# espyolsuz.net
KiCad netlist of a schematic drawn in EAGLE
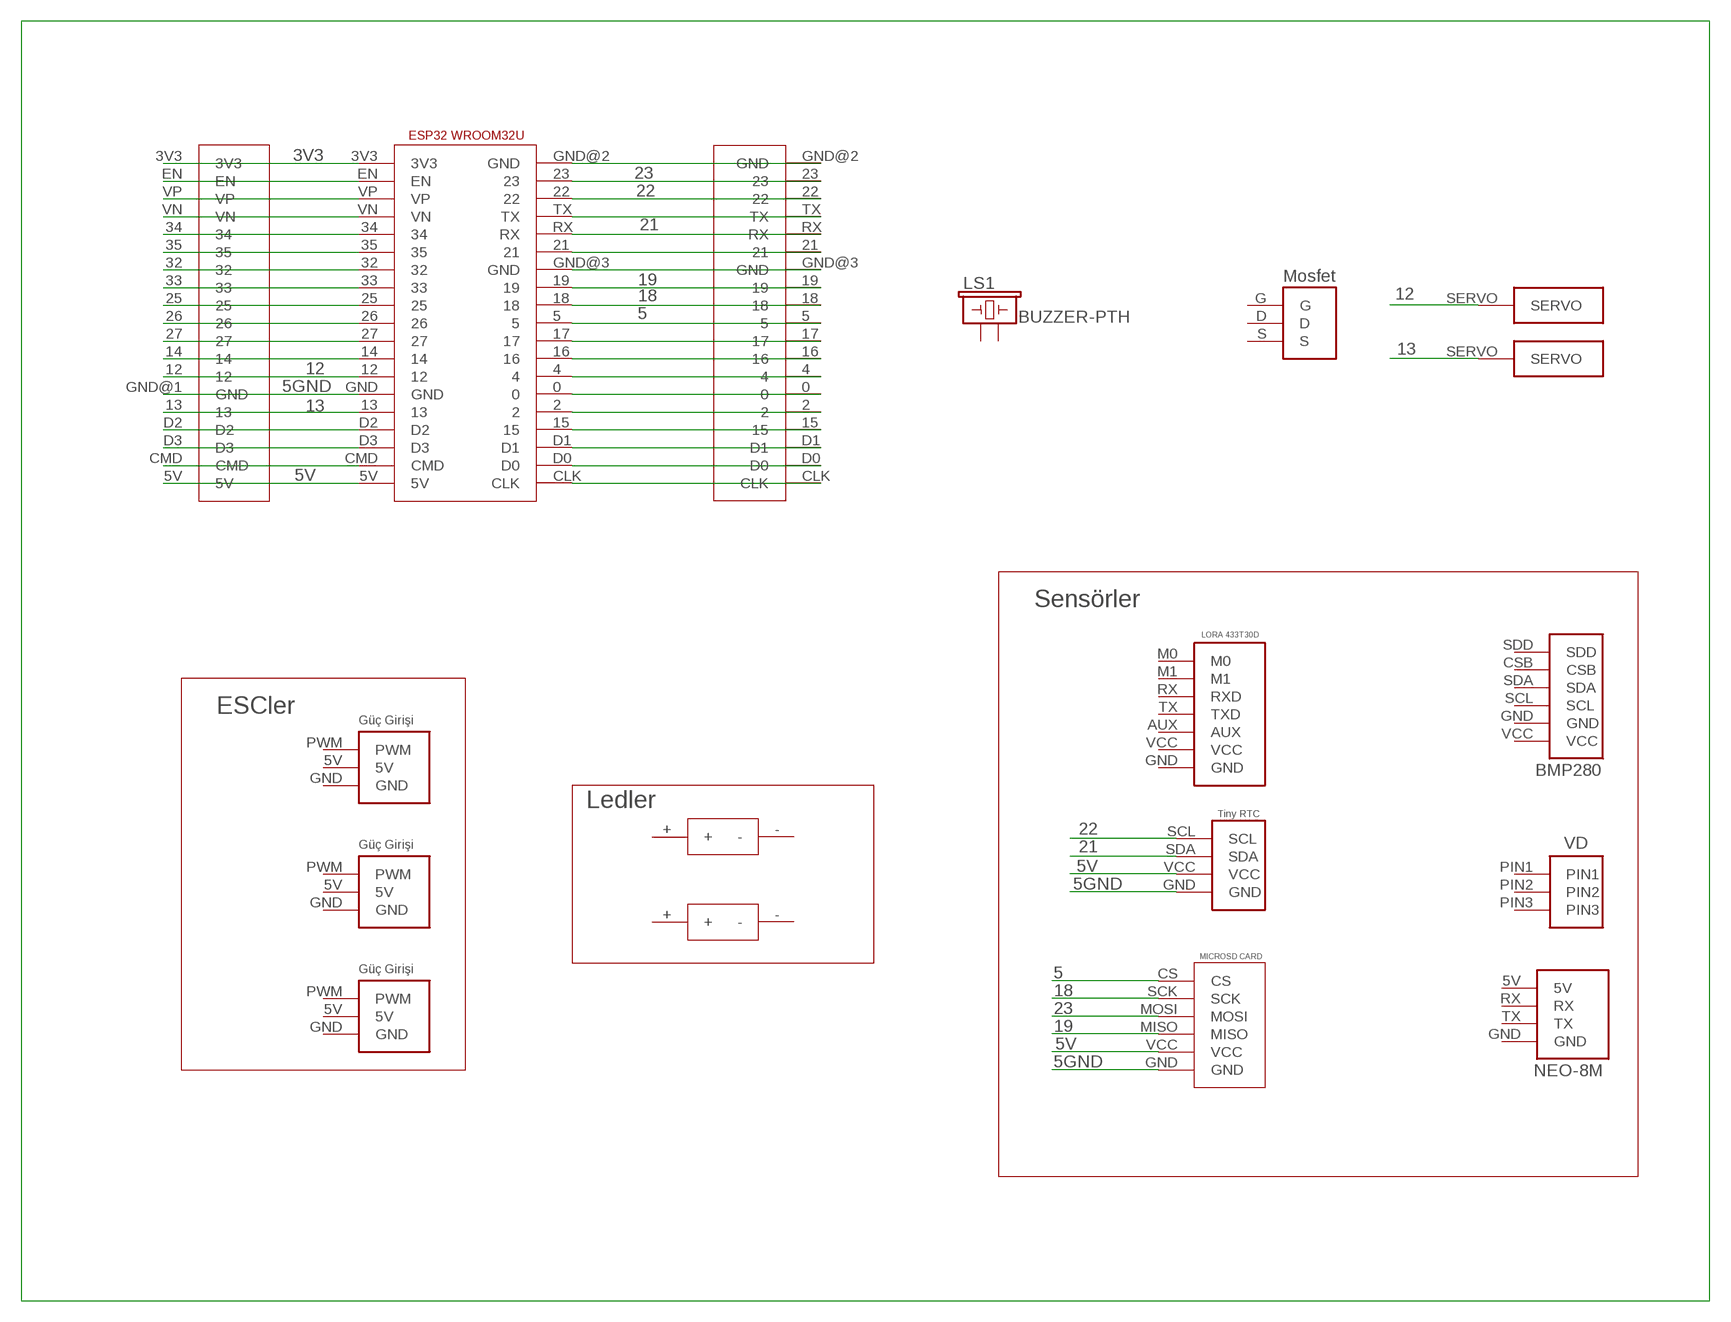
[diagram p0: schematic, sheet 1]

(export (version "E")
  (design (tool "Eeschema 10.0.6"))
  (components
    (comp (ref "BMP1")
      (value "BMP280")
      (footprint "eagle-import:BMP280")
      (libsource (lib "eagle-import") (part "BMP280"))
    )
    (comp (ref "LS1")
      (value "BUZZER-PTH")
      (footprint "eagle-import:BUZZER-12MM")
      (libsource (lib "eagle-import") (part "BUZZER-PTH"))
    )
    (comp (ref "U$1")
      (value "TINYRTC")
      (footprint "eagle-import:TINYRTC")
      (libsource (lib "eagle-import") (part "TINYRTC"))
    )
    (comp (ref "U$2")
      (value "VOLTAGE_DIVIDER")
      (footprint "eagle-import:VOLTAGE_DIVIDER")
      (libsource (lib "eagle-import") (part "VOLTAGE_DIVIDER"))
    )
    (comp (ref "U$3")
      (value "NEOM8N")
      (footprint "eagle-import:NEO8M")
      (libsource (lib "eagle-import") (part "NEOM8N"))
    )
    (comp (ref "U$4")
      (value "ESP32WROOM32U")
      (footprint "eagle-import:ESP32WROOM32U")
      (libsource (lib "eagle-import") (part "ESP32WROOM32U"))
    )
    (comp (ref "U$5")
      (value "LORAFULLSIZE")
      (footprint "eagle-import:LORAFULLSIZE")
      (libsource (lib "eagle-import") (part "LORAFULLSIZE"))
    )
    (comp (ref "U$6")
      (value "MICROSD_CARD")
      (footprint "eagle-import:MICROSD_CARD")
      (libsource (lib "eagle-import") (part "MICROSD_CARD"))
    )
    (comp (ref "U$7")
      (value "SERVO_SIGNAL")
      (footprint "eagle-import:SERVO_SIGNAL")
      (libsource (lib "eagle-import") (part "SERVO_SIGNAL"))
    )
    (comp (ref "U$9")
      (value "SERVO_SIGNAL")
      (footprint "eagle-import:SERVO_SIGNAL")
      (libsource (lib "eagle-import") (part "SERVO_SIGNAL"))
    )
    (comp (ref "U$11")
      (value "ESC_GIRIS")
      (footprint "eagle-import:ESC_GIRIS")
      (libsource (lib "eagle-import") (part "ESC_GIRIS"))
    )
    (comp (ref "U$12")
      (value "ESC_GIRIS")
      (footprint "eagle-import:ESC_GIRIS")
      (libsource (lib "eagle-import") (part "ESC_GIRIS"))
    )
    (comp (ref "U$13")
      (value "ESC_GIRIS")
      (footprint "eagle-import:ESC_GIRIS")
      (libsource (lib "eagle-import") (part "ESC_GIRIS"))
    )
    (comp (ref "U$14")
      (value "ESPSAGPIN")
      (footprint "eagle-import:ESPSAGPIN")
      (libsource (lib "eagle-import") (part "ESPSAGPIN"))
    )
    (comp (ref "U$15")
      (value "ESPSOLPIN")
      (footprint "eagle-import:ESPSOLPIN")
      (libsource (lib "eagle-import") (part "ESPSOLPIN"))
    )
    (comp (ref "U$16")
      (value "MOSFET")
      (footprint "eagle-import:MOSFET")
      (libsource (lib "eagle-import") (part "MOSFET"))
    )
    (comp (ref "U$17")
      (value "LED")
      (footprint "eagle-import:LED")
      (libsource (lib "eagle-import") (part "LED"))
    )
    (comp (ref "U$18")
      (value "LED")
      (footprint "eagle-import:LED")
      (libsource (lib "eagle-import") (part "LED"))
    )
  )
  (nets
    (net (code "1") (name "/3V3") (class "Default")
      (node (ref "U$15") (pin "3V3") (pinfunction "3V3_3V3") (pintype "bidirectional"))
      (node (ref "U$4") (pin "3V3") (pinfunction "3V3_3V3") (pintype "bidirectional"))
    )
    (net (code "2") (name "/5") (class "Default")
      (node (ref "U$14") (pin "5") (pinfunction "5_5") (pintype "bidirectional"))
      (node (ref "U$4") (pin "5") (pinfunction "5_5") (pintype "bidirectional"))
      (node (ref "U$6") (pin "CS") (pinfunction "CS_CS") (pintype "bidirectional"))
    )
    (net (code "3") (name "/5GND") (class "Default")
      (node (ref "U$1") (pin "GND") (pinfunction "GND_GND") (pintype "bidirectional"))
      (node (ref "U$15") (pin "GND@1") (pinfunction "GND_GND@1") (pintype "bidirectional"))
      (node (ref "U$4") (pin "GND") (pinfunction "GND_GND") (pintype "bidirectional"))
      (node (ref "U$6") (pin "GND") (pinfunction "GND_GND") (pintype "bidirectional"))
    )
    (net (code "4") (name "/5V") (class "Default")
      (node (ref "U$1") (pin "VCC") (pinfunction "VCC_VCC") (pintype "bidirectional"))
      (node (ref "U$15") (pin "5V") (pinfunction "5V_5V") (pintype "bidirectional"))
      (node (ref "U$4") (pin "5V") (pinfunction "5V_5V") (pintype "bidirectional"))
      (node (ref "U$6") (pin "VCC") (pinfunction "VCC_VCC") (pintype "bidirectional"))
    )
    (net (code "5") (name "/12") (class "Default")
      (node (ref "U$15") (pin "12") (pinfunction "12_12") (pintype "bidirectional"))
      (node (ref "U$4") (pin "12") (pinfunction "12_12") (pintype "bidirectional"))
      (node (ref "U$7") (pin "SERVO") (pinfunction "SERVO_SERVO") (pintype "bidirectional"))
    )
    (net (code "6") (name "/13") (class "Default")
      (node (ref "U$15") (pin "13") (pinfunction "13_13") (pintype "bidirectional"))
      (node (ref "U$4") (pin "13") (pinfunction "13_13") (pintype "bidirectional"))
      (node (ref "U$9") (pin "SERVO") (pinfunction "SERVO_SERVO") (pintype "bidirectional"))
    )
    (net (code "7") (name "/18") (class "Default")
      (node (ref "U$14") (pin "18") (pinfunction "18_18") (pintype "bidirectional"))
      (node (ref "U$4") (pin "18") (pinfunction "18_18") (pintype "bidirectional"))
      (node (ref "U$6") (pin "SCK") (pinfunction "SCK_SCK") (pintype "bidirectional"))
    )
    (net (code "8") (name "/19") (class "Default")
      (node (ref "U$14") (pin "19") (pinfunction "19_19") (pintype "bidirectional"))
      (node (ref "U$4") (pin "19") (pinfunction "19_19") (pintype "bidirectional"))
      (node (ref "U$6") (pin "MISO") (pinfunction "MISO_MISO") (pintype "bidirectional"))
    )
    (net (code "9") (name "/21") (class "Default")
      (node (ref "U$1") (pin "SDA") (pinfunction "SDA_SDA") (pintype "bidirectional"))
      (node (ref "U$14") (pin "21") (pinfunction "21_21") (pintype "bidirectional"))
      (node (ref "U$4") (pin "21") (pinfunction "21_21") (pintype "bidirectional"))
    )
    (net (code "10") (name "/22") (class "Default")
      (node (ref "U$1") (pin "SCL") (pinfunction "SCL_SCL") (pintype "bidirectional"))
      (node (ref "U$14") (pin "22") (pinfunction "22_22") (pintype "bidirectional"))
      (node (ref "U$4") (pin "22") (pinfunction "22_22") (pintype "bidirectional"))
    )
    (net (code "11") (name "/23") (class "Default")
      (node (ref "U$14") (pin "23") (pinfunction "23_23") (pintype "bidirectional"))
      (node (ref "U$4") (pin "23") (pinfunction "23_23") (pintype "bidirectional"))
      (node (ref "U$6") (pin "MOSI") (pinfunction "MOSI_MOSI") (pintype "bidirectional"))
    )
    (net (code "12") (name "Net-(U$14-GND-PadGND@2)") (class "Default")
      (node (ref "U$14") (pin "GND@2") (pinfunction "GND_GND@2") (pintype "bidirectional"))
      (node (ref "U$4") (pin "GND@2") (pinfunction "GND_GND@2") (pintype "bidirectional"))
    )
    (net (code "13") (name "Net-(U$14-GND-PadGND@3)") (class "Default")
      (node (ref "U$14") (pin "GND@3") (pinfunction "GND_GND@3") (pintype "bidirectional"))
      (node (ref "U$4") (pin "GND@3") (pinfunction "GND_GND@3") (pintype "bidirectional"))
    )
    (net (code "14") (name "Net-(U$14-Pad0)") (class "Default")
      (node (ref "U$14") (pin "0") (pinfunction "0_0") (pintype "bidirectional"))
      (node (ref "U$4") (pin "0") (pinfunction "0_0") (pintype "bidirectional"))
    )
    (net (code "15") (name "Net-(U$14-Pad2)") (class "Default")
      (node (ref "U$14") (pin "2") (pinfunction "2_2") (pintype "bidirectional"))
      (node (ref "U$4") (pin "2") (pinfunction "2_2") (pintype "bidirectional"))
    )
    (net (code "16") (name "Net-(U$14-Pad4)") (class "Default")
      (node (ref "U$14") (pin "4") (pinfunction "4_4") (pintype "bidirectional"))
      (node (ref "U$4") (pin "4") (pinfunction "4_4") (pintype "bidirectional"))
    )
    (net (code "17") (name "Net-(U$14-Pad15)") (class "Default")
      (node (ref "U$14") (pin "15") (pinfunction "15_15") (pintype "bidirectional"))
      (node (ref "U$4") (pin "15") (pinfunction "15_15") (pintype "bidirectional"))
    )
    (net (code "18") (name "Net-(U$14-Pad16)") (class "Default")
      (node (ref "U$14") (pin "16") (pinfunction "16_16") (pintype "bidirectional"))
      (node (ref "U$4") (pin "16") (pinfunction "16_16") (pintype "bidirectional"))
    )
    (net (code "19") (name "Net-(U$14-Pad17)") (class "Default")
      (node (ref "U$14") (pin "17") (pinfunction "17_17") (pintype "bidirectional"))
      (node (ref "U$4") (pin "17") (pinfunction "17_17") (pintype "bidirectional"))
    )
    (net (code "20") (name "Net-(U$14-PadCLK)") (class "Default")
      (node (ref "U$14") (pin "CLK") (pinfunction "CLK_CLK") (pintype "bidirectional"))
      (node (ref "U$4") (pin "CLK") (pinfunction "CLK_CLK") (pintype "bidirectional"))
    )
    (net (code "21") (name "Net-(U$14-PadD0)") (class "Default")
      (node (ref "U$14") (pin "D0") (pinfunction "D0_D0") (pintype "bidirectional"))
      (node (ref "U$4") (pin "D0") (pinfunction "D0_D0") (pintype "bidirectional"))
    )
    (net (code "22") (name "Net-(U$14-PadD1)") (class "Default")
      (node (ref "U$14") (pin "D1") (pinfunction "D1_D1") (pintype "bidirectional"))
      (node (ref "U$4") (pin "D1") (pinfunction "D1_D1") (pintype "bidirectional"))
    )
    (net (code "23") (name "Net-(U$14-PadRX)") (class "Default")
      (node (ref "U$14") (pin "RX") (pinfunction "RX_RX") (pintype "bidirectional"))
      (node (ref "U$4") (pin "RX") (pinfunction "RX_RX") (pintype "bidirectional"))
    )
    (net (code "24") (name "Net-(U$14-PadTX)") (class "Default")
      (node (ref "U$14") (pin "TX") (pinfunction "TX_TX") (pintype "bidirectional"))
      (node (ref "U$4") (pin "TX") (pinfunction "TX_TX") (pintype "bidirectional"))
    )
    (net (code "25") (name "Net-(U$15-Pad14)") (class "Default")
      (node (ref "U$15") (pin "14") (pinfunction "14_14") (pintype "bidirectional"))
      (node (ref "U$4") (pin "14") (pinfunction "14_14") (pintype "bidirectional"))
    )
    (net (code "26") (name "Net-(U$15-Pad25)") (class "Default")
      (node (ref "U$15") (pin "25") (pinfunction "25_25") (pintype "bidirectional"))
      (node (ref "U$4") (pin "25") (pinfunction "25_25") (pintype "bidirectional"))
    )
    (net (code "27") (name "Net-(U$15-Pad26)") (class "Default")
      (node (ref "U$15") (pin "26") (pinfunction "26_26") (pintype "bidirectional"))
      (node (ref "U$4") (pin "26") (pinfunction "26_26") (pintype "bidirectional"))
    )
    (net (code "28") (name "Net-(U$15-Pad27)") (class "Default")
      (node (ref "U$15") (pin "27") (pinfunction "27_27") (pintype "bidirectional"))
      (node (ref "U$4") (pin "27") (pinfunction "27_27") (pintype "bidirectional"))
    )
    (net (code "29") (name "Net-(U$15-Pad32)") (class "Default")
      (node (ref "U$15") (pin "32") (pinfunction "32_32") (pintype "bidirectional"))
      (node (ref "U$4") (pin "32") (pinfunction "32_32") (pintype "bidirectional"))
    )
    (net (code "30") (name "Net-(U$15-Pad33)") (class "Default")
      (node (ref "U$15") (pin "33") (pinfunction "33_33") (pintype "bidirectional"))
      (node (ref "U$4") (pin "33") (pinfunction "33_33") (pintype "bidirectional"))
    )
    (net (code "31") (name "Net-(U$15-Pad34)") (class "Default")
      (node (ref "U$15") (pin "34") (pinfunction "34_34") (pintype "bidirectional"))
      (node (ref "U$4") (pin "34") (pinfunction "34_34") (pintype "bidirectional"))
    )
    (net (code "32") (name "Net-(U$15-Pad35)") (class "Default")
      (node (ref "U$15") (pin "35") (pinfunction "35_35") (pintype "bidirectional"))
      (node (ref "U$4") (pin "35") (pinfunction "35_35") (pintype "bidirectional"))
    )
    (net (code "33") (name "Net-(U$15-PadCMD)") (class "Default")
      (node (ref "U$15") (pin "CMD") (pinfunction "CMD_CMD") (pintype "bidirectional"))
      (node (ref "U$4") (pin "CMD") (pinfunction "CMD_CMD") (pintype "bidirectional"))
    )
    (net (code "34") (name "Net-(U$15-PadD2)") (class "Default")
      (node (ref "U$15") (pin "D2") (pinfunction "D2_D2") (pintype "bidirectional"))
      (node (ref "U$4") (pin "D2") (pinfunction "D2_D2") (pintype "bidirectional"))
    )
    (net (code "35") (name "Net-(U$15-PadD3)") (class "Default")
      (node (ref "U$15") (pin "D3") (pinfunction "D3_D3") (pintype "bidirectional"))
      (node (ref "U$4") (pin "D3") (pinfunction "D3_D3") (pintype "bidirectional"))
    )
    (net (code "36") (name "Net-(U$15-PadEN)") (class "Default")
      (node (ref "U$15") (pin "EN") (pinfunction "EN_EN") (pintype "bidirectional"))
      (node (ref "U$4") (pin "EN") (pinfunction "EN_EN") (pintype "bidirectional"))
    )
    (net (code "37") (name "Net-(U$15-PadVN)") (class "Default")
      (node (ref "U$15") (pin "VN") (pinfunction "VN_VN") (pintype "bidirectional"))
      (node (ref "U$4") (pin "VN") (pinfunction "VN_VN") (pintype "bidirectional"))
    )
    (net (code "38") (name "Net-(U$15-PadVP)") (class "Default")
      (node (ref "U$15") (pin "VP") (pinfunction "VP_VP") (pintype "bidirectional"))
      (node (ref "U$4") (pin "VP") (pinfunction "VP_VP") (pintype "bidirectional"))
    )
    (net (code "39") (name "unconnected-(BMP1-PadCSB)") (class "Default")
      (node (ref "BMP1") (pin "CSB") (pinfunction "CSB_CSB") (pintype "bidirectional"))
    )
    (net (code "40") (name "unconnected-(BMP1-PadGND)") (class "Default")
      (node (ref "BMP1") (pin "GND") (pinfunction "GND_GND") (pintype "bidirectional"))
    )
    (net (code "41") (name "unconnected-(BMP1-PadSCL)") (class "Default")
      (node (ref "BMP1") (pin "SCL") (pinfunction "SCL_SCL") (pintype "bidirectional"))
    )
    (net (code "42") (name "unconnected-(BMP1-PadSDA)") (class "Default")
      (node (ref "BMP1") (pin "SDA") (pinfunction "SDA_SDA") (pintype "bidirectional"))
    )
    (net (code "43") (name "unconnected-(BMP1-PadSDD)") (class "Default")
      (node (ref "BMP1") (pin "SDD") (pinfunction "SDD_SDD") (pintype "bidirectional"))
    )
    (net (code "44") (name "unconnected-(BMP1-PadVCC)") (class "Default")
      (node (ref "BMP1") (pin "VCC") (pinfunction "VCC_VCC") (pintype "bidirectional"))
    )
    (net (code "45") (name "unconnected-(LS1-1-Pad+)") (class "Default")
      (node (ref "LS1") (pin "+") (pinfunction "1_+") (pintype "passive"))
    )
    (net (code "46") (name "unconnected-(LS1-2-Pad-)") (class "Default")
      (node (ref "LS1") (pin "-") (pinfunction "2_-") (pintype "passive"))
    )
    (net (code "47") (name "unconnected-(U$2-PadPIN1)") (class "Default")
      (node (ref "U$2") (pin "PIN1") (pinfunction "PIN1_PIN1") (pintype "bidirectional"))
    )
    (net (code "48") (name "unconnected-(U$2-PadPIN2)") (class "Default")
      (node (ref "U$2") (pin "PIN2") (pinfunction "PIN2_PIN2") (pintype "bidirectional"))
    )
    (net (code "49") (name "unconnected-(U$2-PadPIN3)") (class "Default")
      (node (ref "U$2") (pin "PIN3") (pinfunction "PIN3_PIN3") (pintype "bidirectional"))
    )
    (net (code "50") (name "unconnected-(U$3-Pad5V)") (class "Default")
      (node (ref "U$3") (pin "5V") (pinfunction "5V_5V") (pintype "bidirectional"))
    )
    (net (code "51") (name "unconnected-(U$3-PadGND)") (class "Default")
      (node (ref "U$3") (pin "GND") (pinfunction "GND_GND") (pintype "bidirectional"))
    )
    (net (code "52") (name "unconnected-(U$3-PadRX)") (class "Default")
      (node (ref "U$3") (pin "RX") (pinfunction "RX_RX") (pintype "bidirectional"))
    )
    (net (code "53") (name "unconnected-(U$3-PadTX)") (class "Default")
      (node (ref "U$3") (pin "TX") (pinfunction "TX_TX") (pintype "bidirectional"))
    )
    (net (code "54") (name "unconnected-(U$5-PadAUX)") (class "Default")
      (node (ref "U$5") (pin "AUX") (pinfunction "AUX_AUX") (pintype "bidirectional"))
    )
    (net (code "55") (name "unconnected-(U$5-PadGND)") (class "Default")
      (node (ref "U$5") (pin "GND") (pinfunction "GND_GND") (pintype "bidirectional"))
    )
    (net (code "56") (name "unconnected-(U$5-PadM0)") (class "Default")
      (node (ref "U$5") (pin "M0") (pinfunction "M0_M0") (pintype "bidirectional"))
    )
    (net (code "57") (name "unconnected-(U$5-PadM1)") (class "Default")
      (node (ref "U$5") (pin "M1") (pinfunction "M1_M1") (pintype "bidirectional"))
    )
    (net (code "58") (name "unconnected-(U$5-PadVCC)") (class "Default")
      (node (ref "U$5") (pin "VCC") (pinfunction "VCC_VCC") (pintype "bidirectional"))
    )
    (net (code "59") (name "unconnected-(U$5-RXD-PadRX)") (class "Default")
      (node (ref "U$5") (pin "RX") (pinfunction "RXD_RX") (pintype "bidirectional"))
    )
    (net (code "60") (name "unconnected-(U$5-TXD-PadTX)") (class "Default")
      (node (ref "U$5") (pin "TX") (pinfunction "TXD_TX") (pintype "bidirectional"))
    )
    (net (code "61") (name "unconnected-(U$11-Pad5V)") (class "Default")
      (node (ref "U$11") (pin "5V") (pinfunction "5V_5V") (pintype "bidirectional"))
    )
    (net (code "62") (name "unconnected-(U$11-PadGND)") (class "Default")
      (node (ref "U$11") (pin "GND") (pinfunction "GND_GND") (pintype "bidirectional"))
    )
    (net (code "63") (name "unconnected-(U$11-PadPWM)") (class "Default")
      (node (ref "U$11") (pin "PWM") (pinfunction "PWM_PWM") (pintype "bidirectional"))
    )
    (net (code "64") (name "unconnected-(U$12-Pad5V)") (class "Default")
      (node (ref "U$12") (pin "5V") (pinfunction "5V_5V") (pintype "bidirectional"))
    )
    (net (code "65") (name "unconnected-(U$12-PadGND)") (class "Default")
      (node (ref "U$12") (pin "GND") (pinfunction "GND_GND") (pintype "bidirectional"))
    )
    (net (code "66") (name "unconnected-(U$12-PadPWM)") (class "Default")
      (node (ref "U$12") (pin "PWM") (pinfunction "PWM_PWM") (pintype "bidirectional"))
    )
    (net (code "67") (name "unconnected-(U$13-Pad5V)") (class "Default")
      (node (ref "U$13") (pin "5V") (pinfunction "5V_5V") (pintype "bidirectional"))
    )
    (net (code "68") (name "unconnected-(U$13-PadGND)") (class "Default")
      (node (ref "U$13") (pin "GND") (pinfunction "GND_GND") (pintype "bidirectional"))
    )
    (net (code "69") (name "unconnected-(U$13-PadPWM)") (class "Default")
      (node (ref "U$13") (pin "PWM") (pinfunction "PWM_PWM") (pintype "bidirectional"))
    )
    (net (code "70") (name "unconnected-(U$16-PadD)") (class "Default")
      (node (ref "U$16") (pin "D") (pinfunction "D_D") (pintype "bidirectional"))
    )
    (net (code "71") (name "unconnected-(U$16-PadG)") (class "Default")
      (node (ref "U$16") (pin "G") (pinfunction "G_G") (pintype "bidirectional"))
    )
    (net (code "72") (name "unconnected-(U$16-PadS)") (class "Default")
      (node (ref "U$16") (pin "S") (pinfunction "S_S") (pintype "bidirectional"))
    )
    (net (code "73") (name "unconnected-(U$17-Pad+)") (class "Default")
      (node (ref "U$17") (pin "+") (pinfunction "+_+") (pintype "bidirectional"))
    )
    (net (code "74") (name "unconnected-(U$17-Pad-)") (class "Default")
      (node (ref "U$17") (pin "-") (pinfunction "-_-") (pintype "bidirectional"))
    )
    (net (code "75") (name "unconnected-(U$18-Pad+)") (class "Default")
      (node (ref "U$18") (pin "+") (pinfunction "+_+") (pintype "bidirectional"))
    )
    (net (code "76") (name "unconnected-(U$18-Pad-)") (class "Default")
      (node (ref "U$18") (pin "-") (pinfunction "-_-") (pintype "bidirectional"))
    )
  )
)
